# sheet.net
KiCad netlist of a schematic drawn in Altium Designer
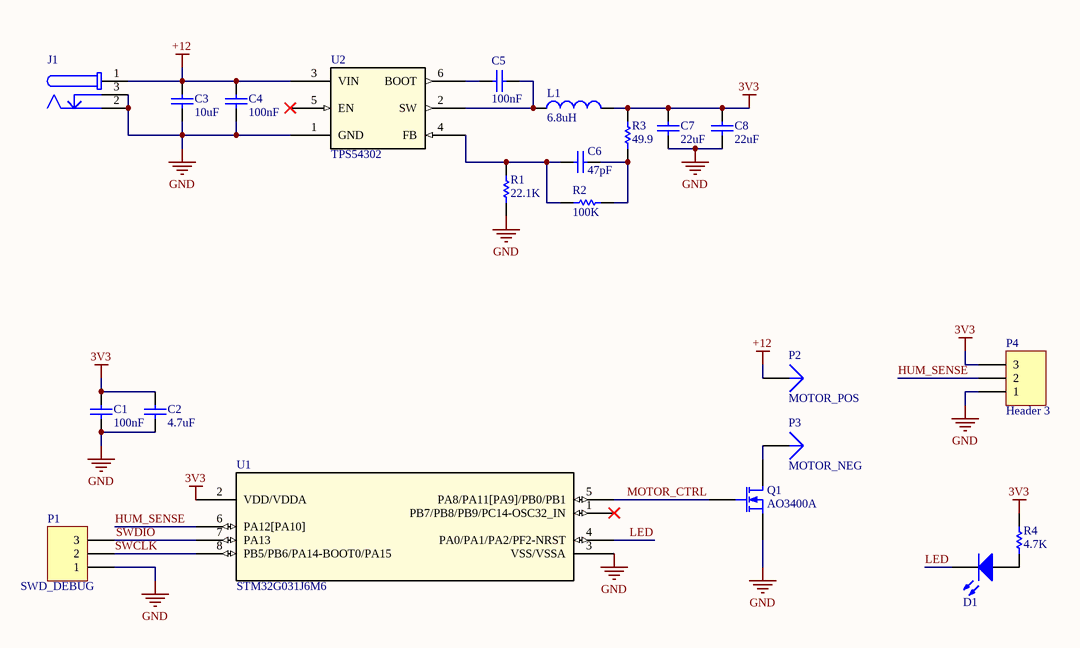
[diagram p0: sheet.SchDoc]

(export (version "E")
  (design (tool "Eeschema 10.0.6"))
  (components
    (comp (ref "C1")
      (value "100nF")
      (footprint "CAP_0603")
      (description "Multilayer Ceramic Capacitors")
      (fields (field (name "TOLERANCE") "10%") (field (name "Comment") "MLCC"))
      (libsource (lib "Capacitors") (part "MLCC"))
    )
    (comp (ref "C2")
      (value "4.7uF")
      (footprint "CAP_0603")
      (description "Multilayer Ceramic Capacitors")
      (fields (field (name "TOLERANCE") "10%") (field (name "Comment") "MLCC"))
      (libsource (lib "Capacitors") (part "MLCC"))
    )
    (comp (ref "C3")
      (value "10uF")
      (footprint "CAP_0603")
      (description "Multilayer Ceramic Capacitors")
      (fields (field (name "TOLERANCE") "10%") (field (name "Comment") "MLCC"))
      (libsource (lib "Capacitors") (part "MLCC"))
    )
    (comp (ref "C4")
      (value "100nF")
      (footprint "CAP_0603")
      (description "Multilayer Ceramic Capacitors")
      (fields (field (name "TOLERANCE") "10%") (field (name "Comment") "MLCC"))
      (libsource (lib "Capacitors") (part "MLCC"))
    )
    (comp (ref "C5")
      (value "100nF")
      (footprint "CAP_0603")
      (description "Multilayer Ceramic Capacitors")
      (fields (field (name "TOLERANCE") "10%") (field (name "Comment") "MLCC"))
      (libsource (lib "Capacitors") (part "MLCC"))
    )
    (comp (ref "C6")
      (value "47pF")
      (footprint "CAP_0603")
      (description "Multilayer Ceramic Capacitors")
      (fields (field (name "TOLERANCE") "10%") (field (name "Comment") "MLCC"))
      (libsource (lib "Capacitors") (part "MLCC"))
    )
    (comp (ref "C7")
      (value "22uF")
      (footprint "CAP_0603")
      (description "Multilayer Ceramic Capacitors")
      (fields (field (name "TOLERANCE") "10%") (field (name "Comment") "MLCC"))
      (libsource (lib "Capacitors") (part "MLCC"))
    )
    (comp (ref "C8")
      (value "22uF")
      (footprint "CAP_0603")
      (description "Multilayer Ceramic Capacitors")
      (fields (field (name "TOLERANCE") "10%") (field (name "Comment") "MLCC"))
      (libsource (lib "Capacitors") (part "MLCC"))
    )
    (comp (ref "D1")
      (value "LED")
      (footprint "0603_GREEN")
      (description "LED Emitters")
      (libsource (lib "Leds") (part "LED"))
    )
    (comp (ref "J1")
      (value "DC Power Jacks")
      (footprint "DC POWER JACK (1)")
      (description "DC Power Jack Connector with 4 soldering pads & Pegs WR-DC, Male, Right Angled, SMT, 5 A, 24 V")
      (libsource (lib "Connectors") (part "DC Power Jacks"))
    )
    (comp (ref "L1")
      (value "6.8uH")
      (footprint "INDWW_4mmSQ")
      (description "Fixed Inductors")
      (fields (field (name "Comment") "Inductor"))
      (libsource (lib "Inductors") (part "Inductor"))
    )
    (comp (ref "P1")
      (value "SWD_DEBUG")
      (footprint "HDR1X3")
      (description "Header, 3-Pin")
      (fields (field (name "PUBLISHER") "Altium Limited"))
      (libsource (lib "Miscellaneous Connectors") (part "Header 3"))
    )
    (comp (ref "P2")
      (value "MOTOR_POS")
      (footprint "PIN1")
      (description "Plug")
      (fields (field (name "PUBLISHER") "Altium Limited"))
      (libsource (lib "Miscellaneous Connectors") (part "Plug"))
    )
    (comp (ref "P3")
      (value "MOTOR_NEG")
      (footprint "PIN1")
      (description "Plug")
      (fields (field (name "PUBLISHER") "Altium Limited"))
      (libsource (lib "Miscellaneous Connectors") (part "Plug"))
    )
    (comp (ref "P4")
      (value "Header 3")
      (footprint "HDR1X3")
      (description "Header, 3-Pin")
      (fields (field (name "PUBLISHER") "Altium Limited"))
      (libsource (lib "") (part "Header 3_1"))
    )
    (comp (ref "Q1")
      (value "AO3400A")
      (footprint "SOT-23/TO-236_318-08")
      (description "N-Channel MOSFET")
      (fields (field (name "PUBLISHER") "Altium Limited"))
      (libsource (lib "Miscellaneous Devices") (part "MOSFET-N"))
    )
    (comp (ref "R1")
      (value "22.1K")
      (footprint "RC0603N")
      (description "Chip Resistors")
      (fields (field (name "Comment") "RES"))
      (libsource (lib "Resistors") (part "RES"))
    )
    (comp (ref "R2")
      (value "100K")
      (footprint "RC0603N")
      (description "Chip Resistors")
      (fields (field (name "Comment") "RES"))
      (libsource (lib "Resistors") (part "RES"))
    )
    (comp (ref "R3")
      (value "49.9")
      (footprint "RC0603N")
      (description "Chip Resistors")
      (fields (field (name "Comment") "RES"))
      (libsource (lib "Resistors") (part "RES"))
    )
    (comp (ref "R4")
      (value "4.7K")
      (footprint "RC0603N")
      (description "Chip Resistors")
      (fields (field (name "Comment") "RES"))
      (libsource (lib "Resistors") (part "RES"))
    )
    (comp (ref "U1")
      (value "STM32G031J6M6")
      (footprint "SO8N")
      (fields (field (name "COPYRIGHT") "Copyright (C) 2018 Accelerated Designs. All rights reserved"))
      (libsource (lib "ST") (part "STM32G031J6M6"))
    )
    (comp (ref "U2")
      (value "TPS54302")
      (footprint "DDC6")
      (description "TPS54302 4.5-V to 28-V Input, 3-A Output, EMI Friendly\r\nSynchronous Step-Down Converter")
      (fields
        (field (name "MANUFACTURER") "Texas Instruments")
        (field (name "MANUFACTURER_PART_NUMBER") "TPS54302DDCR")
        (field (name "COPYRIGHT") "Copyright (C) 2020 MWLabs. All rights reserved")
      )
      (libsource (lib "TI") (part "TPS54302"))
    )
  )
  (nets
    (net (code "1") (name "+12") (class "Default")
      (node (ref "C3") (pin "2") (pinfunction "2_2") (pintype "passive"))
      (node (ref "C4") (pin "2") (pinfunction "2_2") (pintype "passive"))
      (node (ref "J1") (pin "1") (pinfunction "1_1") (pintype "passive"))
      (node (ref "P2") (pin "1") (pinfunction "1_1") (pintype "passive"))
      (node (ref "U2") (pin "3") (pinfunction "VIN_3") (pintype "power_in"))
    )
    (net (code "2") (name "/HUM_SENSE") (class "Default")
      (node (ref "P4") (pin "2") (pinfunction "2_2") (pintype "passive"))
      (node (ref "U1") (pin "6") (pinfunction "PA12[PA10]_6") (pintype "bidirectional"))
    )
    (net (code "3") (name "/LED") (class "Default")
      (node (ref "D1") (pin "2") (pinfunction "K_2") (pintype "passive"))
      (node (ref "U1") (pin "4") (pinfunction "PA0/PA1/PA2/PF2-NRST_4") (pintype "bidirectional"))
    )
    (net (code "4") (name "/MOTOR_CTRL") (class "Default")
      (node (ref "Q1") (pin "2") (pinfunction "G_2") (pintype "passive"))
      (node (ref "U1") (pin "5") (pinfunction "PA8/PA11[PA9]/PB0/PB1_5") (pintype "bidirectional"))
    )
    (net (code "5") (name "/SWCLK") (class "Default")
      (node (ref "P1") (pin "2") (pinfunction "2_2") (pintype "passive"))
      (node (ref "U1") (pin "8") (pinfunction "PB5/PB6/PA14-BOOT0/PA15_8") (pintype "bidirectional"))
    )
    (net (code "6") (name "/SWDIO") (class "Default")
      (node (ref "P1") (pin "3") (pinfunction "3_3") (pintype "passive"))
      (node (ref "U1") (pin "7") (pinfunction "PA13_7") (pintype "bidirectional"))
    )
    (net (code "7") (name "3V3") (class "Default")
      (node (ref "C1") (pin "2") (pinfunction "2_2") (pintype "passive"))
      (node (ref "C2") (pin "2") (pinfunction "2_2") (pintype "passive"))
      (node (ref "C7") (pin "1") (pinfunction "1_1") (pintype "passive"))
      (node (ref "C8") (pin "1") (pinfunction "1_1") (pintype "passive"))
      (node (ref "L1") (pin "2") (pinfunction "2_2") (pintype "passive"))
      (node (ref "P4") (pin "3") (pinfunction "3_3") (pintype "passive"))
      (node (ref "R3") (pin "2") (pinfunction "2_2") (pintype "passive"))
      (node (ref "R4") (pin "2") (pinfunction "2_2") (pintype "passive"))
      (node (ref "U1") (pin "2") (pinfunction "VDD/VDDA_2") (pintype "power_in"))
    )
    (net (code "8") (name "GND") (class "Default")
      (node (ref "C1") (pin "1") (pinfunction "1_1") (pintype "passive"))
      (node (ref "C2") (pin "1") (pinfunction "1_1") (pintype "passive"))
      (node (ref "C3") (pin "1") (pinfunction "1_1") (pintype "passive"))
      (node (ref "C4") (pin "1") (pinfunction "1_1") (pintype "passive"))
      (node (ref "C7") (pin "2") (pinfunction "2_2") (pintype "passive"))
      (node (ref "C8") (pin "2") (pinfunction "2_2") (pintype "passive"))
      (node (ref "J1") (pin "2") (pinfunction "2_2") (pintype "passive"))
      (node (ref "J1") (pin "3") (pinfunction "3_3") (pintype "passive"))
      (node (ref "P1") (pin "1") (pinfunction "1_1") (pintype "passive"))
      (node (ref "P4") (pin "1") (pinfunction "1_1") (pintype "passive"))
      (node (ref "Q1") (pin "3") (pinfunction "S_3") (pintype "passive"))
      (node (ref "R1") (pin "1") (pinfunction "1_1") (pintype "passive"))
      (node (ref "U1") (pin "3") (pinfunction "VSS/VSSA_3") (pintype "power_in"))
      (node (ref "U2") (pin "1") (pinfunction "GND_1") (pintype "power_in"))
    )
    (net (code "9") (name "Net-(C6-Pad2)") (class "Default")
      (node (ref "C6") (pin "2") (pinfunction "2_2") (pintype "passive"))
      (node (ref "R2") (pin "1") (pinfunction "1_1") (pintype "passive"))
      (node (ref "R3") (pin "1") (pinfunction "1_1") (pintype "passive"))
    )
    (net (code "10") (name "Net-(D1-A)") (class "Default")
      (node (ref "D1") (pin "1") (pinfunction "A_1") (pintype "passive"))
      (node (ref "R4") (pin "1") (pinfunction "1_1") (pintype "passive"))
    )
    (net (code "11") (name "Net-(Q1-D)") (class "Default")
      (node (ref "P3") (pin "1") (pinfunction "1_1") (pintype "passive"))
      (node (ref "Q1") (pin "1") (pinfunction "D_1") (pintype "passive"))
    )
    (net (code "12") (name "Net-(U2-BOOT)") (class "Default")
      (node (ref "C5") (pin "2") (pinfunction "2_2") (pintype "passive"))
      (node (ref "U2") (pin "6") (pinfunction "BOOT_6") (pintype "output"))
    )
    (net (code "13") (name "Net-(U2-FB)") (class "Default")
      (node (ref "C6") (pin "1") (pinfunction "1_1") (pintype "passive"))
      (node (ref "R1") (pin "2") (pinfunction "2_2") (pintype "passive"))
      (node (ref "R2") (pin "2") (pinfunction "2_2") (pintype "passive"))
      (node (ref "U2") (pin "4") (pinfunction "FB_4") (pintype "input"))
    )
    (net (code "14") (name "Net-(U2-SW)") (class "Default")
      (node (ref "C5") (pin "1") (pinfunction "1_1") (pintype "passive"))
      (node (ref "L1") (pin "1") (pinfunction "1_1") (pintype "passive"))
      (node (ref "U2") (pin "2") (pinfunction "SW_2") (pintype "output"))
    )
    (net (code "15") (name "unconnected-(U1-PB7{slash}PB8{slash}PB9{slash}PC14-OSC32_IN-Pad1)") (class "Default")
      (node (ref "U1") (pin "1") (pinfunction "PB7/PB8/PB9/PC14-OSC32_IN_1") (pintype "bidirectional+no_connect"))
    )
    (net (code "16") (name "unconnected-(U2-EN-Pad5)") (class "Default")
      (node (ref "U2") (pin "5") (pinfunction "EN_5") (pintype "input+no_connect"))
    )
  )
)
